# 04-bottom.net
KiCad netlist of a schematic drawn in EAGLE
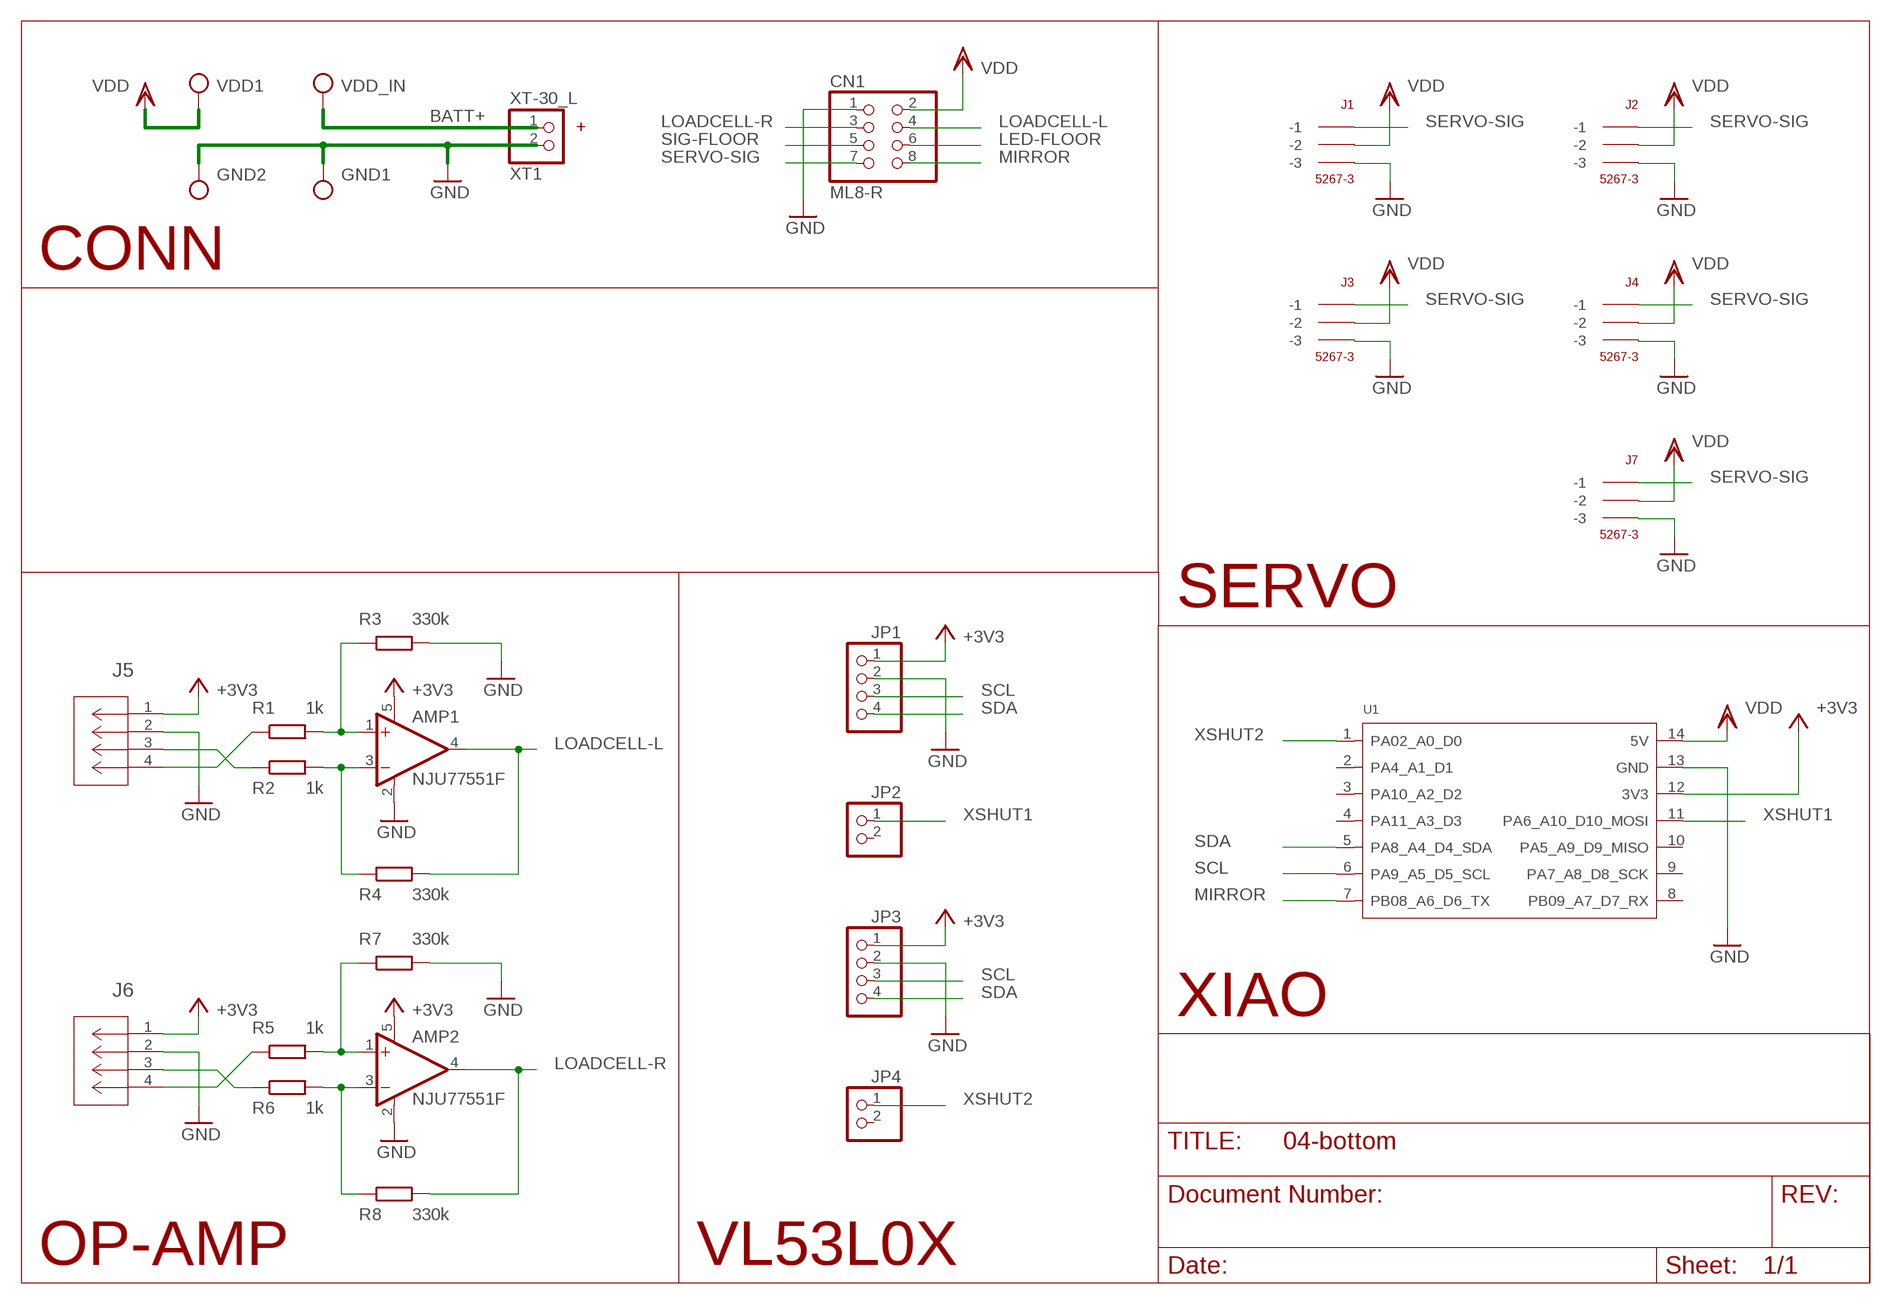
[diagram p0: schematic, sheet 1]

(export (version "E")
  (design (tool "Eeschema 10.0.6"))
  (components
    (comp (ref "AMP1")
      (value "NJU77551F")
      (footprint "eagle-import:SOT23-5")
      (libsource (lib "eagle-import") (part "NJU77551F"))
    )
    (comp (ref "AMP2")
      (value "NJU77551F")
      (footprint "eagle-import:SOT23-5")
      (libsource (lib "eagle-import") (part "NJU77551F"))
    )
    (comp (ref "CN1")
      (value "ML8-R")
      (footprint "eagle-import:ML6")
      (libsource (lib "eagle-import") (part "ML8-R"))
    )
    (comp (ref "GND1")
      (value "PAD_GND")
      (footprint "eagle-import:GND")
      (libsource (lib "eagle-import") (part "PAD_GND"))
    )
    (comp (ref "GND2")
      (value "PAD_GND")
      (footprint "eagle-import:GND")
      (libsource (lib "eagle-import") (part "PAD_GND"))
    )
    (comp (ref "J1")
      (value "5267-3")
      (footprint "eagle-import:5267-3")
      (libsource (lib "eagle-import") (part "5267-3"))
    )
    (comp (ref "J2")
      (value "5267-3")
      (footprint "eagle-import:5267-3")
      (libsource (lib "eagle-import") (part "5267-3"))
    )
    (comp (ref "J3")
      (value "5267-3")
      (footprint "eagle-import:5267-3")
      (libsource (lib "eagle-import") (part "5267-3"))
    )
    (comp (ref "J4")
      (value "5267-3")
      (footprint "eagle-import:5267-3")
      (libsource (lib "eagle-import") (part "5267-3"))
    )
    (comp (ref "J5")
      (value "22057045")
      (footprint "eagle-import:CON_22057045_MOL")
      (fields (field (name "COPYRIGHT") "Copyright (C) 2022 Ultra Librarian. All rights reserved."))
      (libsource (lib "eagle-import") (part "22057045"))
    )
    (comp (ref "J6")
      (value "22057045")
      (footprint "eagle-import:CON_22057045_MOL")
      (fields (field (name "COPYRIGHT") "Copyright (C) 2022 Ultra Librarian. All rights reserved."))
      (libsource (lib "eagle-import") (part "22057045"))
    )
    (comp (ref "J7")
      (value "5267-3")
      (footprint "eagle-import:5267-3")
      (libsource (lib "eagle-import") (part "5267-3"))
    )
    (comp (ref "JP1")
      (value "PINHD-1X4")
      (footprint "eagle-import:1X04")
      (libsource (lib "eagle-import") (part "PINHD-1X4"))
    )
    (comp (ref "JP2")
      (value "PINHD-1X2")
      (footprint "eagle-import:1X02")
      (libsource (lib "eagle-import") (part "PINHD-1X2"))
    )
    (comp (ref "JP3")
      (value "PINHD-1X4")
      (footprint "eagle-import:1X04")
      (libsource (lib "eagle-import") (part "PINHD-1X4"))
    )
    (comp (ref "JP4")
      (value "PINHD-1X2")
      (footprint "eagle-import:1X02")
      (libsource (lib "eagle-import") (part "PINHD-1X2"))
    )
    (comp (ref "R1")
      (value "1k")
      (footprint "eagle-import:R0805")
      (libsource (lib "eagle-import") (part "R-EU_R0805"))
    )
    (comp (ref "R2")
      (value "1k")
      (footprint "eagle-import:R0805")
      (libsource (lib "eagle-import") (part "R-EU_R0805"))
    )
    (comp (ref "R3")
      (value "330k")
      (footprint "eagle-import:R0805")
      (libsource (lib "eagle-import") (part "R-EU_R0805"))
    )
    (comp (ref "R4")
      (value "330k")
      (footprint "eagle-import:R0805")
      (libsource (lib "eagle-import") (part "R-EU_R0805"))
    )
    (comp (ref "R5")
      (value "1k")
      (footprint "eagle-import:R0805")
      (libsource (lib "eagle-import") (part "R-EU_R0805"))
    )
    (comp (ref "R6")
      (value "1k")
      (footprint "eagle-import:R0805")
      (libsource (lib "eagle-import") (part "R-EU_R0805"))
    )
    (comp (ref "R7")
      (value "330k")
      (footprint "eagle-import:R0805")
      (libsource (lib "eagle-import") (part "R-EU_R0805"))
    )
    (comp (ref "R8")
      (value "330k")
      (footprint "eagle-import:R0805")
      (libsource (lib "eagle-import") (part "R-EU_R0805"))
    )
    (comp (ref "U1")
      (value "MOUDLE-SEEEDUINO-XIAO")
      (footprint "eagle-import:MOUDLE14P-2.54-21X17.8MM")
      (libsource (lib "eagle-import") (part "MOUDLE-SEEEDUINO-XIAO"))
    )
    (comp (ref "VDD1")
      (value "PAD_VDD")
      (footprint "eagle-import:VDD")
      (libsource (lib "eagle-import") (part "PAD_VDD"))
    )
    (comp (ref "VDD_IN")
      (value "PAD_VDD")
      (footprint "eagle-import:VDD")
      (libsource (lib "eagle-import") (part "PAD_VDD"))
    )
    (comp (ref "XT1")
      (value "XT-30_L")
      (footprint "eagle-import:XT-30_L")
      (libsource (lib "eagle-import") (part "XT-30_L"))
    )
  )
  (nets
    (net (code "1") (name "+3V3") (class "Default")
      (node (ref "AMP1") (pin "5") (pinfunction "V+_5") (pintype "power_in"))
      (node (ref "AMP2") (pin "5") (pinfunction "V+_5") (pintype "power_in"))
      (node (ref "J5") (pin "1") (pinfunction "1_1") (pintype "passive"))
      (node (ref "J6") (pin "1") (pinfunction "1_1") (pintype "passive"))
      (node (ref "JP1") (pin "1") (pinfunction "1_1") (pintype "passive"))
      (node (ref "JP3") (pin "1") (pinfunction "1_1") (pintype "passive"))
      (node (ref "U1") (pin "12") (pinfunction "3V3_12") (pintype "bidirectional"))
    )
    (net (code "2") (name "/BATT+") (class "Default")
      (node (ref "VDD_IN") (pin "P$1") (pinfunction "TP_P$1") (pintype "input"))
      (node (ref "XT1") (pin "1") (pinfunction "1_1") (pintype "passive"))
    )
    (net (code "3") (name "/LED-FLOOR") (class "Default")
      (node (ref "CN1") (pin "6") (pinfunction "6_6") (pintype "passive"))
    )
    (net (code "4") (name "/LOADCELL-L") (class "Default")
      (node (ref "AMP1") (pin "4") (pinfunction "OUT_4") (pintype "output"))
      (node (ref "CN1") (pin "4") (pinfunction "4_4") (pintype "passive"))
      (node (ref "R4") (pin "2") (pinfunction "2_2") (pintype "passive"))
    )
    (net (code "5") (name "/LOADCELL-R") (class "Default")
      (node (ref "AMP2") (pin "4") (pinfunction "OUT_4") (pintype "output"))
      (node (ref "CN1") (pin "3") (pinfunction "3_3") (pintype "passive"))
      (node (ref "R8") (pin "2") (pinfunction "2_2") (pintype "passive"))
    )
    (net (code "6") (name "/MIRROR") (class "Default")
      (node (ref "CN1") (pin "8") (pinfunction "8_8") (pintype "passive"))
      (node (ref "U1") (pin "7") (pinfunction "PB08_A6_D6_TX_7") (pintype "bidirectional"))
    )
    (net (code "7") (name "/SCL") (class "Default")
      (node (ref "JP1") (pin "3") (pinfunction "3_3") (pintype "passive"))
      (node (ref "JP3") (pin "3") (pinfunction "3_3") (pintype "passive"))
      (node (ref "U1") (pin "6") (pinfunction "PA9_A5_D5_SCL_6") (pintype "bidirectional"))
    )
    (net (code "8") (name "/SDA") (class "Default")
      (node (ref "JP1") (pin "4") (pinfunction "4_4") (pintype "passive"))
      (node (ref "JP3") (pin "4") (pinfunction "4_4") (pintype "passive"))
      (node (ref "U1") (pin "5") (pinfunction "PA8_A4_D4_SDA_5") (pintype "bidirectional"))
    )
    (net (code "9") (name "/SERVO-SIG") (class "Default")
      (node (ref "CN1") (pin "7") (pinfunction "7_7") (pintype "passive"))
      (node (ref "J1") (pin "P$1") (pinfunction "-1_P$1") (pintype "bidirectional"))
      (node (ref "J2") (pin "P$1") (pinfunction "-1_P$1") (pintype "bidirectional"))
      (node (ref "J3") (pin "P$1") (pinfunction "-1_P$1") (pintype "bidirectional"))
      (node (ref "J4") (pin "P$1") (pinfunction "-1_P$1") (pintype "bidirectional"))
      (node (ref "J7") (pin "P$1") (pinfunction "-1_P$1") (pintype "bidirectional"))
    )
    (net (code "10") (name "/SIG-FLOOR") (class "Default")
      (node (ref "CN1") (pin "5") (pinfunction "5_5") (pintype "passive"))
    )
    (net (code "11") (name "/XSHUT1") (class "Default")
      (node (ref "JP2") (pin "1") (pinfunction "1_1") (pintype "passive"))
      (node (ref "U1") (pin "11") (pinfunction "PA6_A10_D10_MOSI_11") (pintype "bidirectional"))
    )
    (net (code "12") (name "/XSHUT2") (class "Default")
      (node (ref "JP4") (pin "1") (pinfunction "1_1") (pintype "passive"))
      (node (ref "U1") (pin "1") (pinfunction "PA02_A0_D0_1") (pintype "bidirectional"))
    )
    (net (code "13") (name "GND") (class "Default")
      (node (ref "AMP1") (pin "2") (pinfunction "V-_2") (pintype "power_in"))
      (node (ref "AMP2") (pin "2") (pinfunction "V-_2") (pintype "power_in"))
      (node (ref "CN1") (pin "1") (pinfunction "1_1") (pintype "passive"))
      (node (ref "GND1") (pin "P$1") (pinfunction "TP_P$1") (pintype "input"))
      (node (ref "GND2") (pin "P$1") (pinfunction "TP_P$1") (pintype "input"))
      (node (ref "J1") (pin "P$3") (pinfunction "-3_P$3") (pintype "bidirectional"))
      (node (ref "J2") (pin "P$3") (pinfunction "-3_P$3") (pintype "bidirectional"))
      (node (ref "J3") (pin "P$3") (pinfunction "-3_P$3") (pintype "bidirectional"))
      (node (ref "J4") (pin "P$3") (pinfunction "-3_P$3") (pintype "bidirectional"))
      (node (ref "J5") (pin "2") (pinfunction "2_2") (pintype "passive"))
      (node (ref "J6") (pin "2") (pinfunction "2_2") (pintype "passive"))
      (node (ref "J7") (pin "P$3") (pinfunction "-3_P$3") (pintype "bidirectional"))
      (node (ref "JP1") (pin "2") (pinfunction "2_2") (pintype "passive"))
      (node (ref "JP3") (pin "2") (pinfunction "2_2") (pintype "passive"))
      (node (ref "R3") (pin "2") (pinfunction "2_2") (pintype "passive"))
      (node (ref "R7") (pin "2") (pinfunction "2_2") (pintype "passive"))
      (node (ref "U1") (pin "13") (pinfunction "GND_13") (pintype "bidirectional"))
      (node (ref "XT1") (pin "2") (pinfunction "2_2") (pintype "passive"))
    )
    (net (code "14") (name "Net-(AMP1-+IN)") (class "Default")
      (node (ref "AMP1") (pin "1") (pinfunction "+IN_1") (pintype "input"))
      (node (ref "R1") (pin "2") (pinfunction "2_2") (pintype "passive"))
      (node (ref "R3") (pin "1") (pinfunction "1_1") (pintype "passive"))
    )
    (net (code "15") (name "Net-(AMP1--IN)") (class "Default")
      (node (ref "AMP1") (pin "3") (pinfunction "-IN_3") (pintype "input"))
      (node (ref "R2") (pin "2") (pinfunction "2_2") (pintype "passive"))
      (node (ref "R4") (pin "1") (pinfunction "1_1") (pintype "passive"))
    )
    (net (code "16") (name "Net-(AMP2-+IN)") (class "Default")
      (node (ref "AMP2") (pin "1") (pinfunction "+IN_1") (pintype "input"))
      (node (ref "R5") (pin "2") (pinfunction "2_2") (pintype "passive"))
      (node (ref "R7") (pin "1") (pinfunction "1_1") (pintype "passive"))
    )
    (net (code "17") (name "Net-(AMP2--IN)") (class "Default")
      (node (ref "AMP2") (pin "3") (pinfunction "-IN_3") (pintype "input"))
      (node (ref "R6") (pin "2") (pinfunction "2_2") (pintype "passive"))
      (node (ref "R8") (pin "1") (pinfunction "1_1") (pintype "passive"))
    )
    (net (code "18") (name "Net-(J5-Pad3)") (class "Default")
      (node (ref "J5") (pin "3") (pinfunction "3_3") (pintype "passive"))
      (node (ref "R2") (pin "1") (pinfunction "1_1") (pintype "passive"))
    )
    (net (code "19") (name "Net-(J5-Pad4)") (class "Default")
      (node (ref "J5") (pin "4") (pinfunction "4_4") (pintype "passive"))
      (node (ref "R1") (pin "1") (pinfunction "1_1") (pintype "passive"))
    )
    (net (code "20") (name "Net-(J6-Pad3)") (class "Default")
      (node (ref "J6") (pin "3") (pinfunction "3_3") (pintype "passive"))
      (node (ref "R6") (pin "1") (pinfunction "1_1") (pintype "passive"))
    )
    (net (code "21") (name "Net-(J6-Pad4)") (class "Default")
      (node (ref "J6") (pin "4") (pinfunction "4_4") (pintype "passive"))
      (node (ref "R5") (pin "1") (pinfunction "1_1") (pintype "passive"))
    )
    (net (code "22") (name "VDD") (class "Default")
      (node (ref "CN1") (pin "2") (pinfunction "2_2") (pintype "passive"))
      (node (ref "J1") (pin "P$2") (pinfunction "-2_P$2") (pintype "bidirectional"))
      (node (ref "J2") (pin "P$2") (pinfunction "-2_P$2") (pintype "bidirectional"))
      (node (ref "J3") (pin "P$2") (pinfunction "-2_P$2") (pintype "bidirectional"))
      (node (ref "J4") (pin "P$2") (pinfunction "-2_P$2") (pintype "bidirectional"))
      (node (ref "J7") (pin "P$2") (pinfunction "-2_P$2") (pintype "bidirectional"))
      (node (ref "U1") (pin "14") (pinfunction "5V_14") (pintype "bidirectional"))
      (node (ref "VDD1") (pin "P$1") (pinfunction "TP_P$1") (pintype "input"))
    )
    (net (code "23") (name "unconnected-(JP2-Pad2)") (class "Default")
      (node (ref "JP2") (pin "2") (pinfunction "2_2") (pintype "passive"))
    )
    (net (code "24") (name "unconnected-(JP4-Pad2)") (class "Default")
      (node (ref "JP4") (pin "2") (pinfunction "2_2") (pintype "passive"))
    )
    (net (code "25") (name "unconnected-(U1-PA4_A1_D1-Pad2)") (class "Default")
      (node (ref "U1") (pin "2") (pinfunction "PA4_A1_D1_2") (pintype "bidirectional"))
    )
    (net (code "26") (name "unconnected-(U1-PA5_A9_D9_MISO-Pad10)") (class "Default")
      (node (ref "U1") (pin "10") (pinfunction "PA5_A9_D9_MISO_10") (pintype "bidirectional"))
    )
    (net (code "27") (name "unconnected-(U1-PA7_A8_D8_SCK-Pad9)") (class "Default")
      (node (ref "U1") (pin "9") (pinfunction "PA7_A8_D8_SCK_9") (pintype "bidirectional"))
    )
    (net (code "28") (name "unconnected-(U1-PA10_A2_D2-Pad3)") (class "Default")
      (node (ref "U1") (pin "3") (pinfunction "PA10_A2_D2_3") (pintype "bidirectional"))
    )
    (net (code "29") (name "unconnected-(U1-PA11_A3_D3-Pad4)") (class "Default")
      (node (ref "U1") (pin "4") (pinfunction "PA11_A3_D3_4") (pintype "bidirectional"))
    )
    (net (code "30") (name "unconnected-(U1-PB09_A7_D7_RX-Pad8)") (class "Default")
      (node (ref "U1") (pin "8") (pinfunction "PB09_A7_D7_RX_8") (pintype "bidirectional"))
    )
  )
)
